# Mircrocontroller-test-moudle.net
KiCad netlist of a schematic drawn in EAGLE
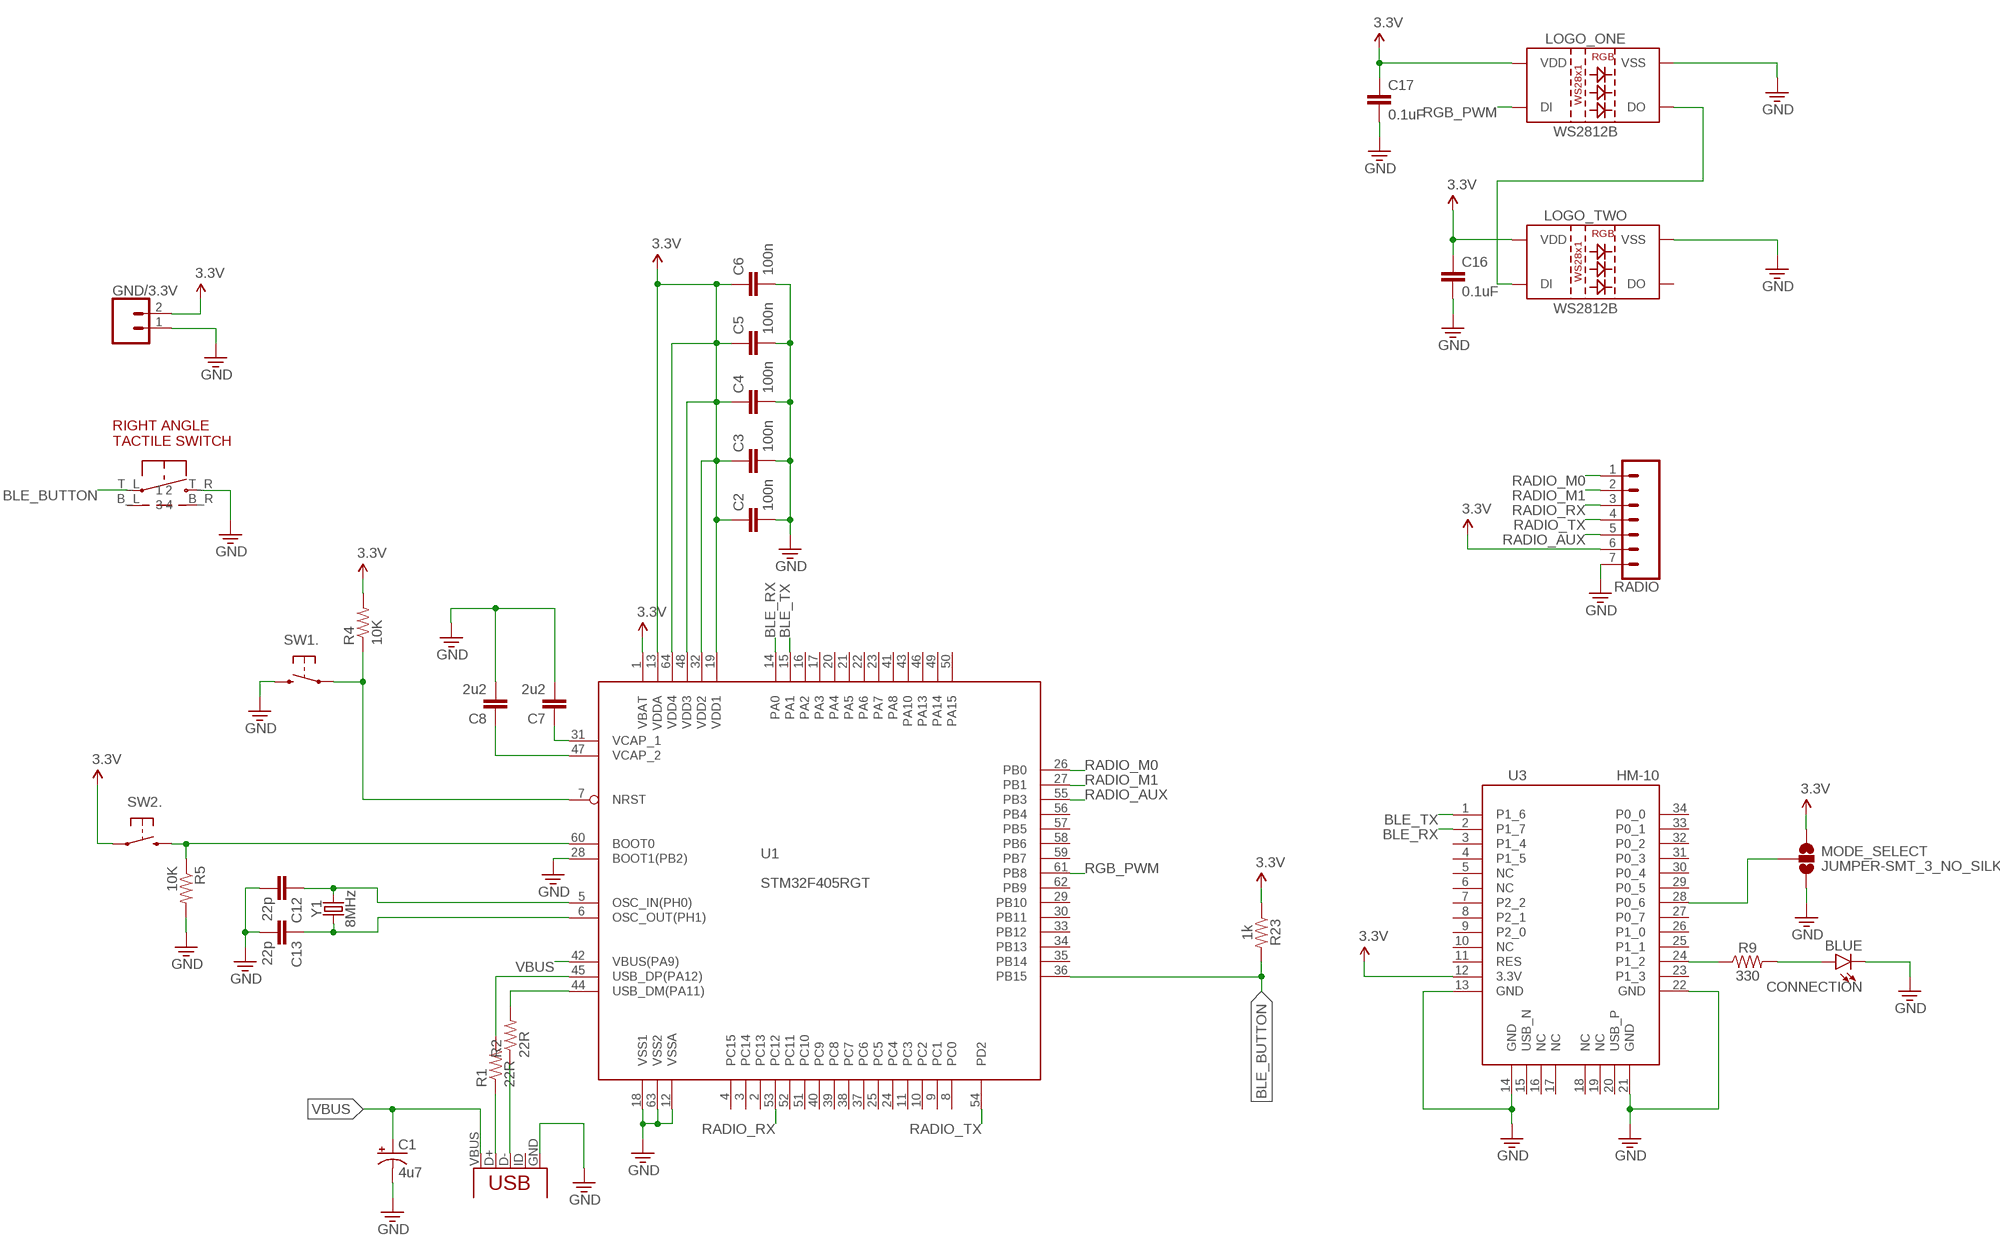
[diagram p0: schematic, sheet 1]

(export (version "E")
  (design (tool "Eeschema 10.0.6"))
  (components
    (comp (ref "C1")
      (value "4u7")
      (footprint "eagle-import:EIA3216-KIT")
      (libsource (lib "eagle-import") (part "CAP_POL1206-KIT"))
    )
    (comp (ref "C2")
      (value "100n")
      (footprint "eagle-import:0603-CAP")
      (libsource (lib "eagle-import") (part "CAP0603-CAP"))
    )
    (comp (ref "C3")
      (value "100n")
      (footprint "eagle-import:0603-CAP")
      (libsource (lib "eagle-import") (part "CAP0603-CAP"))
    )
    (comp (ref "C4")
      (value "100n")
      (footprint "eagle-import:0603-CAP")
      (libsource (lib "eagle-import") (part "CAP0603-CAP"))
    )
    (comp (ref "C5")
      (value "100n")
      (footprint "eagle-import:0603-CAP")
      (libsource (lib "eagle-import") (part "CAP0603-CAP"))
    )
    (comp (ref "C6")
      (value "100n")
      (footprint "eagle-import:0603-CAP")
      (libsource (lib "eagle-import") (part "CAP0603-CAP"))
    )
    (comp (ref "C7")
      (value "2u2")
      (footprint "eagle-import:0603-CAP")
      (libsource (lib "eagle-import") (part "CAP0603-CAP"))
    )
    (comp (ref "C8")
      (value "2u2")
      (footprint "eagle-import:0603-CAP")
      (libsource (lib "eagle-import") (part "CAP0603-CAP"))
    )
    (comp (ref "C12")
      (value "22p")
      (footprint "eagle-import:0603-CAP")
      (libsource (lib "eagle-import") (part "CAP0603-CAP"))
    )
    (comp (ref "C13")
      (value "22p")
      (footprint "eagle-import:0603-CAP")
      (libsource (lib "eagle-import") (part "CAP0603-CAP"))
    )
    (comp (ref "C16")
      (value "0.1uF")
      (footprint "eagle-import:0603")
      (libsource (lib "eagle-import") (part "0.1UF-0603-25V-5%"))
    )
    (comp (ref "C17")
      (value "0.1uF")
      (footprint "eagle-import:0603")
      (libsource (lib "eagle-import") (part "0.1UF-0603-25V-5%"))
    )
    (comp (ref "CONNECTION")
      (value "BLUE")
      (footprint "eagle-import:LED-0603")
      (libsource (lib "eagle-import") (part "LED-BLUE0603"))
    )
    (comp (ref "GND/3.3V")
      (value "CONN_02LOCK")
      (footprint "eagle-import:1X02_LOCK")
      (libsource (lib "eagle-import") (part "CONN_02LOCK"))
    )
    (comp (ref "LOGO_ONE")
      (value "WS2812B")
      (footprint "eagle-import:WS2812B")
      (libsource (lib "eagle-import") (part "WS2812B"))
    )
    (comp (ref "LOGO_TWO")
      (value "WS2812B")
      (footprint "eagle-import:WS2812B")
      (libsource (lib "eagle-import") (part "WS2812B"))
    )
    (comp (ref "MODE_SELECT")
      (value "JUMPER-SMT_3_NO_SILK")
      (footprint "eagle-import:SMT-JUMPER_3_NO_SILK")
      (libsource (lib "eagle-import") (part "JUMPER-SMT_3_NO_SILK"))
    )
    (comp (ref "R1")
      (value "22R")
      (footprint "eagle-import:0603-RES")
      (libsource (lib "eagle-import") (part "RESISTOR0603-RES"))
    )
    (comp (ref "R2")
      (value "22R")
      (footprint "eagle-import:0603-RES")
      (libsource (lib "eagle-import") (part "RESISTOR0603-RES"))
    )
    (comp (ref "R4")
      (value "10K")
      (footprint "eagle-import:0603-RES")
      (libsource (lib "eagle-import") (part "RESISTOR0603-RES"))
    )
    (comp (ref "R5")
      (value "10K")
      (footprint "eagle-import:0603-RES")
      (libsource (lib "eagle-import") (part "RESISTOR0603-RES"))
    )
    (comp (ref "R9")
      (value "330")
      (footprint "eagle-import:0603")
      (libsource (lib "eagle-import") (part "330OHM-0603-1/10W-1%"))
    )
    (comp (ref "R23")
      (value "1k")
      (footprint "eagle-import:0603")
      (libsource (lib "eagle-import") (part "1KOHM-0603-1/10W-1%"))
    )
    (comp (ref "RADIO")
      (value "CONN_07")
      (footprint "eagle-import:1X07")
      (libsource (lib "eagle-import") (part "CONN_07"))
    )
    (comp (ref "SW1")
      (value "!RST")
      (footprint "eagle-import:SWITCH-TACT-B3U-1100P-B")
      (libsource (lib "eagle-import") (part "SWITCH-B3U-1110-BOSS"))
    )
    (comp (ref "SW2")
      (value "BOOT")
      (footprint "eagle-import:SWITCH-TACT-B3U-1100P-B")
      (libsource (lib "eagle-import") (part "SWITCH-B3U-1110-BOSS"))
    )
    (comp (ref "U$1")
      (value "RIGHT_ANGLE_TACTILE_SWITCH")
      (footprint "eagle-import:RIGHT_ANGLE_TACTILE_SWITCH")
      (libsource (lib "eagle-import") (part "RIGHT_ANGLE_TACTILE_SWITCH"))
    )
    (comp (ref "U1")
      (value "STM32F405RGT")
      (footprint "eagle-import:LQFP64")
      (libsource (lib "eagle-import") (part "STM32F405RGT"))
    )
    (comp (ref "U3")
      (value "HM-10")
      (footprint "eagle-import:HM-10")
      (libsource (lib "eagle-import") (part "HM-10"))
    )
    (comp (ref "USB")
      (value "USB-MICROB-SMD")
      (footprint "eagle-import:USB-MICROB-SMD")
      (libsource (lib "eagle-import") (part "USB-MICROB-SMD"))
    )
    (comp (ref "Y1")
      (value "8MHz")
      (footprint "eagle-import:CRYSTAL-SMD-5X3.2-4PAD")
      (libsource (lib "eagle-import") (part "CRYSTAL-8MHZSMD-5X3.2"))
    )
  )
  (nets
    (net (code "1") (name "/BLE_RX") (class "Default")
      (node (ref "U1") (pin "14") (pinfunction "PA0_14") (pintype "bidirectional"))
      (node (ref "U3") (pin "2") (pinfunction "P1_7_2") (pintype "bidirectional"))
    )
    (net (code "2") (name "/BLE_TX") (class "Default")
      (node (ref "U1") (pin "15") (pinfunction "PA1_15") (pintype "bidirectional"))
      (node (ref "U3") (pin "1") (pinfunction "P1_6_1") (pintype "bidirectional"))
    )
    (net (code "3") (name "/RADIO_AUX") (class "Default")
      (node (ref "RADIO") (pin "5") (pinfunction "5_5") (pintype "passive"))
      (node (ref "U1") (pin "55") (pinfunction "PB3_55") (pintype "bidirectional"))
    )
    (net (code "4") (name "/RADIO_M0") (class "Default")
      (node (ref "RADIO") (pin "1") (pinfunction "1_1") (pintype "passive"))
      (node (ref "U1") (pin "26") (pinfunction "PB0_26") (pintype "bidirectional"))
    )
    (net (code "5") (name "/RADIO_M1") (class "Default")
      (node (ref "RADIO") (pin "2") (pinfunction "2_2") (pintype "passive"))
      (node (ref "U1") (pin "27") (pinfunction "PB1_27") (pintype "bidirectional"))
    )
    (net (code "6") (name "/RADIO_RX") (class "Default")
      (node (ref "RADIO") (pin "3") (pinfunction "3_3") (pintype "passive"))
      (node (ref "U1") (pin "53") (pinfunction "PC12_53") (pintype "bidirectional"))
    )
    (net (code "7") (name "/RADIO_TX") (class "Default")
      (node (ref "RADIO") (pin "4") (pinfunction "4_4") (pintype "passive"))
      (node (ref "U1") (pin "54") (pinfunction "PD2_54") (pintype "bidirectional"))
    )
    (net (code "8") (name "/RGB_PWM") (class "Default")
      (node (ref "LOGO_ONE") (pin "4") (pinfunction "DI_4") (pintype "bidirectional"))
      (node (ref "U1") (pin "61") (pinfunction "PB8_61") (pintype "bidirectional"))
    )
    (net (code "9") (name "3.3V") (class "Default")
      (node (ref "C16") (pin "1") (pinfunction "1_1") (pintype "passive"))
      (node (ref "C17") (pin "1") (pinfunction "1_1") (pintype "passive"))
      (node (ref "C2") (pin "1") (pinfunction "1_1") (pintype "passive"))
      (node (ref "C3") (pin "1") (pinfunction "1_1") (pintype "passive"))
      (node (ref "C4") (pin "1") (pinfunction "1_1") (pintype "passive"))
      (node (ref "C5") (pin "1") (pinfunction "1_1") (pintype "passive"))
      (node (ref "C6") (pin "1") (pinfunction "1_1") (pintype "passive"))
      (node (ref "GND/3.3V") (pin "2") (pinfunction "2_2") (pintype "passive"))
      (node (ref "LOGO_ONE") (pin "1") (pinfunction "VDD_1") (pintype "bidirectional"))
      (node (ref "LOGO_TWO") (pin "1") (pinfunction "VDD_1") (pintype "bidirectional"))
      (node (ref "MODE_SELECT") (pin "1") (pinfunction "1_1") (pintype "passive"))
      (node (ref "R23") (pin "1") (pinfunction "1_1") (pintype "passive"))
      (node (ref "R4") (pin "2") (pinfunction "2_2") (pintype "passive"))
      (node (ref "RADIO") (pin "6") (pinfunction "6_6") (pintype "passive"))
      (node (ref "SW2") (pin "1") (pinfunction "1_1") (pintype "passive"))
      (node (ref "U1") (pin "1") (pinfunction "VBAT_1") (pintype "power_in"))
      (node (ref "U1") (pin "13") (pinfunction "VDDA_13") (pintype "power_in"))
      (node (ref "U1") (pin "19") (pinfunction "VDD1_19") (pintype "power_in"))
      (node (ref "U1") (pin "32") (pinfunction "VDD2_32") (pintype "power_in"))
      (node (ref "U1") (pin "48") (pinfunction "VDD3_48") (pintype "power_in"))
      (node (ref "U1") (pin "64") (pinfunction "VDD4_64") (pintype "power_in"))
      (node (ref "U3") (pin "12") (pinfunction "3.3V_12") (pintype "bidirectional"))
    )
    (net (code "10") (name "BLE_BUTTON") (class "Default")
      (node (ref "R23") (pin "2") (pinfunction "2_2") (pintype "passive"))
      (node (ref "U$1") (pin "T_L") (pinfunction "1_T_L") (pintype "bidirectional"))
      (node (ref "U1") (pin "36") (pinfunction "PB15_36") (pintype "bidirectional"))
    )
    (net (code "11") (name "GND") (class "Default")
      (node (ref "C1") (pin "C") (pinfunction "-_C") (pintype "passive"))
      (node (ref "C12") (pin "2") (pinfunction "2_2") (pintype "passive"))
      (node (ref "C13") (pin "2") (pinfunction "2_2") (pintype "passive"))
      (node (ref "C16") (pin "2") (pinfunction "2_2") (pintype "passive"))
      (node (ref "C17") (pin "2") (pinfunction "2_2") (pintype "passive"))
      (node (ref "C2") (pin "2") (pinfunction "2_2") (pintype "passive"))
      (node (ref "C3") (pin "2") (pinfunction "2_2") (pintype "passive"))
      (node (ref "C4") (pin "2") (pinfunction "2_2") (pintype "passive"))
      (node (ref "C5") (pin "2") (pinfunction "2_2") (pintype "passive"))
      (node (ref "C6") (pin "2") (pinfunction "2_2") (pintype "passive"))
      (node (ref "C7") (pin "2") (pinfunction "2_2") (pintype "passive"))
      (node (ref "C8") (pin "2") (pinfunction "2_2") (pintype "passive"))
      (node (ref "CONNECTION") (pin "C") (pinfunction "C_C") (pintype "passive"))
      (node (ref "GND/3.3V") (pin "1") (pinfunction "1_1") (pintype "passive"))
      (node (ref "LOGO_ONE") (pin "3") (pinfunction "VSS_3") (pintype "bidirectional"))
      (node (ref "LOGO_TWO") (pin "3") (pinfunction "VSS_3") (pintype "bidirectional"))
      (node (ref "MODE_SELECT") (pin "3") (pinfunction "3_3") (pintype "passive"))
      (node (ref "R5") (pin "2") (pinfunction "2_2") (pintype "passive"))
      (node (ref "RADIO") (pin "7") (pinfunction "7_7") (pintype "passive"))
      (node (ref "SW1") (pin "2") (pinfunction "2_2") (pintype "passive"))
      (node (ref "U$1") (pin "T_R") (pinfunction "2_T_R") (pintype "bidirectional"))
      (node (ref "U1") (pin "12") (pinfunction "VSSA_12") (pintype "power_in"))
      (node (ref "U1") (pin "18") (pinfunction "VSS1_18") (pintype "power_in"))
      (node (ref "U1") (pin "28") (pinfunction "BOOT1(PB2)_28") (pintype "input"))
      (node (ref "U1") (pin "63") (pinfunction "VSS2_63") (pintype "power_in"))
      (node (ref "U3") (pin "13") (pinfunction "GND_13") (pintype "bidirectional"))
      (node (ref "U3") (pin "14") (pinfunction "GND_14") (pintype "bidirectional"))
      (node (ref "U3") (pin "21") (pinfunction "GND_21") (pintype "bidirectional"))
      (node (ref "U3") (pin "22") (pinfunction "GND_22") (pintype "bidirectional"))
      (node (ref "USB") (pin "GND") (pinfunction "GND_GND") (pintype "bidirectional"))
    )
    (net (code "12") (name "Net-(CONNECTION-PadA)") (class "Default")
      (node (ref "CONNECTION") (pin "A") (pinfunction "A_A") (pintype "passive"))
      (node (ref "R9") (pin "2") (pinfunction "2_2") (pintype "passive"))
    )
    (net (code "13") (name "Net-(LOGO_ONE-DO)") (class "Default")
      (node (ref "LOGO_ONE") (pin "2") (pinfunction "DO_2") (pintype "bidirectional"))
      (node (ref "LOGO_TWO") (pin "4") (pinfunction "DI_4") (pintype "bidirectional"))
    )
    (net (code "14") (name "Net-(R1-Pad1)") (class "Default")
      (node (ref "R1") (pin "1") (pinfunction "1_1") (pintype "passive"))
      (node (ref "USB") (pin "D+") (pinfunction "D+_D+") (pintype "bidirectional"))
    )
    (net (code "15") (name "Net-(R2-Pad1)") (class "Default")
      (node (ref "R2") (pin "1") (pinfunction "1_1") (pintype "passive"))
      (node (ref "USB") (pin "D-") (pinfunction "D-_D-") (pintype "bidirectional"))
    )
    (net (code "16") (name "Net-(U1-BOOT0)") (class "Default")
      (node (ref "R5") (pin "1") (pinfunction "1_1") (pintype "passive"))
      (node (ref "SW2") (pin "2") (pinfunction "2_2") (pintype "passive"))
      (node (ref "U1") (pin "60") (pinfunction "BOOT0_60") (pintype "input"))
    )
    (net (code "17") (name "Net-(U1-NRST)") (class "Default")
      (node (ref "R4") (pin "1") (pinfunction "1_1") (pintype "passive"))
      (node (ref "SW1") (pin "1") (pinfunction "1_1") (pintype "passive"))
      (node (ref "U1") (pin "7") (pinfunction "NRST_7") (pintype "input"))
    )
    (net (code "18") (name "Net-(U1-OSC_IN(PH0))") (class "Default")
      (node (ref "C12") (pin "1") (pinfunction "1_1") (pintype "passive"))
      (node (ref "U1") (pin "5") (pinfunction "OSC_IN(PH0)_5") (pintype "bidirectional"))
      (node (ref "Y1") (pin "3") (pinfunction "2_3") (pintype "passive"))
    )
    (net (code "19") (name "Net-(U1-OSC_OUT(PH1))") (class "Default")
      (node (ref "C13") (pin "1") (pinfunction "1_1") (pintype "passive"))
      (node (ref "U1") (pin "6") (pinfunction "OSC_OUT(PH1)_6") (pintype "bidirectional"))
      (node (ref "Y1") (pin "1") (pinfunction "1_1") (pintype "passive"))
    )
    (net (code "20") (name "Net-(U1-USB_DM(PA11))") (class "Default")
      (node (ref "R2") (pin "2") (pinfunction "2_2") (pintype "passive"))
      (node (ref "U1") (pin "44") (pinfunction "USB_DM(PA11)_44") (pintype "bidirectional"))
    )
    (net (code "21") (name "Net-(U1-USB_DP(PA12))") (class "Default")
      (node (ref "R1") (pin "2") (pinfunction "2_2") (pintype "passive"))
      (node (ref "U1") (pin "45") (pinfunction "USB_DP(PA12)_45") (pintype "bidirectional"))
    )
    (net (code "22") (name "Net-(U1-VCAP_1)") (class "Default")
      (node (ref "C7") (pin "1") (pinfunction "1_1") (pintype "passive"))
      (node (ref "U1") (pin "31") (pinfunction "VCAP_1_31") (pintype "bidirectional"))
    )
    (net (code "23") (name "Net-(U1-VCAP_2)") (class "Default")
      (node (ref "C8") (pin "1") (pinfunction "1_1") (pintype "passive"))
      (node (ref "U1") (pin "47") (pinfunction "VCAP_2_47") (pintype "bidirectional"))
    )
    (net (code "24") (name "Net-(U3-P0_6)") (class "Default")
      (node (ref "MODE_SELECT") (pin "2") (pinfunction "2_2") (pintype "passive"))
      (node (ref "U3") (pin "28") (pinfunction "P0_6_28") (pintype "bidirectional"))
    )
    (net (code "25") (name "Net-(U3-P1_2)") (class "Default")
      (node (ref "R9") (pin "1") (pinfunction "1_1") (pintype "passive"))
      (node (ref "U3") (pin "24") (pinfunction "P1_2_24") (pintype "bidirectional"))
    )
    (net (code "26") (name "VBUS") (class "Default")
      (node (ref "C1") (pin "A") (pinfunction "+_A") (pintype "passive"))
      (node (ref "U1") (pin "42") (pinfunction "VBUS(PA9)_42") (pintype "bidirectional"))
      (node (ref "USB") (pin "VBUS") (pinfunction "VBUS_VBUS") (pintype "bidirectional"))
    )
    (net (code "27") (name "unconnected-(LOGO_TWO-DO-Pad2)") (class "Default")
      (node (ref "LOGO_TWO") (pin "2") (pinfunction "DO_2") (pintype "bidirectional"))
    )
    (net (code "28") (name "unconnected-(U$1-3-PadB_L)") (class "Default")
      (node (ref "U$1") (pin "B_L") (pinfunction "3_B_L") (pintype "bidirectional"))
    )
    (net (code "29") (name "unconnected-(U$1-4-PadB_R)") (class "Default")
      (node (ref "U$1") (pin "B_R") (pinfunction "4_B_R") (pintype "bidirectional"))
    )
    (net (code "30") (name "unconnected-(U1-PA2-Pad16)") (class "Default")
      (node (ref "U1") (pin "16") (pinfunction "PA2_16") (pintype "bidirectional"))
    )
    (net (code "31") (name "unconnected-(U1-PA3-Pad17)") (class "Default")
      (node (ref "U1") (pin "17") (pinfunction "PA3_17") (pintype "bidirectional"))
    )
    (net (code "32") (name "unconnected-(U1-PA4-Pad20)") (class "Default")
      (node (ref "U1") (pin "20") (pinfunction "PA4_20") (pintype "bidirectional"))
    )
    (net (code "33") (name "unconnected-(U1-PA5-Pad21)") (class "Default")
      (node (ref "U1") (pin "21") (pinfunction "PA5_21") (pintype "bidirectional"))
    )
    (net (code "34") (name "unconnected-(U1-PA6-Pad22)") (class "Default")
      (node (ref "U1") (pin "22") (pinfunction "PA6_22") (pintype "bidirectional"))
    )
    (net (code "35") (name "unconnected-(U1-PA7-Pad23)") (class "Default")
      (node (ref "U1") (pin "23") (pinfunction "PA7_23") (pintype "bidirectional"))
    )
    (net (code "36") (name "unconnected-(U1-PA8-Pad41)") (class "Default")
      (node (ref "U1") (pin "41") (pinfunction "PA8_41") (pintype "bidirectional"))
    )
    (net (code "37") (name "unconnected-(U1-PA10-Pad43)") (class "Default")
      (node (ref "U1") (pin "43") (pinfunction "PA10_43") (pintype "bidirectional"))
    )
    (net (code "38") (name "unconnected-(U1-PA13-Pad46)") (class "Default")
      (node (ref "U1") (pin "46") (pinfunction "PA13_46") (pintype "bidirectional"))
    )
    (net (code "39") (name "unconnected-(U1-PA14-Pad49)") (class "Default")
      (node (ref "U1") (pin "49") (pinfunction "PA14_49") (pintype "bidirectional"))
    )
    (net (code "40") (name "unconnected-(U1-PA15-Pad50)") (class "Default")
      (node (ref "U1") (pin "50") (pinfunction "PA15_50") (pintype "bidirectional"))
    )
    (net (code "41") (name "unconnected-(U1-PB4-Pad56)") (class "Default")
      (node (ref "U1") (pin "56") (pinfunction "PB4_56") (pintype "bidirectional"))
    )
    (net (code "42") (name "unconnected-(U1-PB5-Pad57)") (class "Default")
      (node (ref "U1") (pin "57") (pinfunction "PB5_57") (pintype "bidirectional"))
    )
    (net (code "43") (name "unconnected-(U1-PB6-Pad58)") (class "Default")
      (node (ref "U1") (pin "58") (pinfunction "PB6_58") (pintype "bidirectional"))
    )
    (net (code "44") (name "unconnected-(U1-PB7-Pad59)") (class "Default")
      (node (ref "U1") (pin "59") (pinfunction "PB7_59") (pintype "bidirectional"))
    )
    (net (code "45") (name "unconnected-(U1-PB9-Pad62)") (class "Default")
      (node (ref "U1") (pin "62") (pinfunction "PB9_62") (pintype "bidirectional"))
    )
    (net (code "46") (name "unconnected-(U1-PB10-Pad29)") (class "Default")
      (node (ref "U1") (pin "29") (pinfunction "PB10_29") (pintype "bidirectional"))
    )
    (net (code "47") (name "unconnected-(U1-PB11-Pad30)") (class "Default")
      (node (ref "U1") (pin "30") (pinfunction "PB11_30") (pintype "bidirectional"))
    )
    (net (code "48") (name "unconnected-(U1-PB12-Pad33)") (class "Default")
      (node (ref "U1") (pin "33") (pinfunction "PB12_33") (pintype "bidirectional"))
    )
    (net (code "49") (name "unconnected-(U1-PB13-Pad34)") (class "Default")
      (node (ref "U1") (pin "34") (pinfunction "PB13_34") (pintype "bidirectional"))
    )
    (net (code "50") (name "unconnected-(U1-PB14-Pad35)") (class "Default")
      (node (ref "U1") (pin "35") (pinfunction "PB14_35") (pintype "bidirectional"))
    )
    (net (code "51") (name "unconnected-(U1-PC0-Pad8)") (class "Default")
      (node (ref "U1") (pin "8") (pinfunction "PC0_8") (pintype "bidirectional"))
    )
    (net (code "52") (name "unconnected-(U1-PC1-Pad9)") (class "Default")
      (node (ref "U1") (pin "9") (pinfunction "PC1_9") (pintype "bidirectional"))
    )
    (net (code "53") (name "unconnected-(U1-PC2-Pad10)") (class "Default")
      (node (ref "U1") (pin "10") (pinfunction "PC2_10") (pintype "bidirectional"))
    )
    (net (code "54") (name "unconnected-(U1-PC3-Pad11)") (class "Default")
      (node (ref "U1") (pin "11") (pinfunction "PC3_11") (pintype "bidirectional"))
    )
    (net (code "55") (name "unconnected-(U1-PC4-Pad24)") (class "Default")
      (node (ref "U1") (pin "24") (pinfunction "PC4_24") (pintype "bidirectional"))
    )
    (net (code "56") (name "unconnected-(U1-PC5-Pad25)") (class "Default")
      (node (ref "U1") (pin "25") (pinfunction "PC5_25") (pintype "bidirectional"))
    )
    (net (code "57") (name "unconnected-(U1-PC6-Pad37)") (class "Default")
      (node (ref "U1") (pin "37") (pinfunction "PC6_37") (pintype "bidirectional"))
    )
    (net (code "58") (name "unconnected-(U1-PC7-Pad38)") (class "Default")
      (node (ref "U1") (pin "38") (pinfunction "PC7_38") (pintype "bidirectional"))
    )
    (net (code "59") (name "unconnected-(U1-PC8-Pad39)") (class "Default")
      (node (ref "U1") (pin "39") (pinfunction "PC8_39") (pintype "bidirectional"))
    )
    (net (code "60") (name "unconnected-(U1-PC9-Pad40)") (class "Default")
      (node (ref "U1") (pin "40") (pinfunction "PC9_40") (pintype "bidirectional"))
    )
    (net (code "61") (name "unconnected-(U1-PC10-Pad51)") (class "Default")
      (node (ref "U1") (pin "51") (pinfunction "PC10_51") (pintype "bidirectional"))
    )
    (net (code "62") (name "unconnected-(U1-PC11-Pad52)") (class "Default")
      (node (ref "U1") (pin "52") (pinfunction "PC11_52") (pintype "bidirectional"))
    )
    (net (code "63") (name "unconnected-(U1-PC13-Pad2)") (class "Default")
      (node (ref "U1") (pin "2") (pinfunction "PC13_2") (pintype "bidirectional"))
    )
    (net (code "64") (name "unconnected-(U1-PC14-Pad3)") (class "Default")
      (node (ref "U1") (pin "3") (pinfunction "PC14_3") (pintype "bidirectional"))
    )
    (net (code "65") (name "unconnected-(U1-PC15-Pad4)") (class "Default")
      (node (ref "U1") (pin "4") (pinfunction "PC15_4") (pintype "bidirectional"))
    )
    (net (code "66") (name "unconnected-(U3-NC-Pad5)") (class "Default")
      (node (ref "U3") (pin "5") (pinfunction "NC_5") (pintype "bidirectional"))
    )
    (net (code "67") (name "unconnected-(U3-NC-Pad6)") (class "Default")
      (node (ref "U3") (pin "6") (pinfunction "NC_6") (pintype "bidirectional"))
    )
    (net (code "68") (name "unconnected-(U3-NC-Pad10)") (class "Default")
      (node (ref "U3") (pin "10") (pinfunction "NC_10") (pintype "bidirectional"))
    )
    (net (code "69") (name "unconnected-(U3-NC-Pad16)") (class "Default")
      (node (ref "U3") (pin "16") (pinfunction "NC_16") (pintype "bidirectional"))
    )
    (net (code "70") (name "unconnected-(U3-NC-Pad17)") (class "Default")
      (node (ref "U3") (pin "17") (pinfunction "NC_17") (pintype "bidirectional"))
    )
    (net (code "71") (name "unconnected-(U3-NC-Pad18)") (class "Default")
      (node (ref "U3") (pin "18") (pinfunction "NC_18") (pintype "bidirectional"))
    )
    (net (code "72") (name "unconnected-(U3-NC-Pad19)") (class "Default")
      (node (ref "U3") (pin "19") (pinfunction "NC_19") (pintype "bidirectional"))
    )
    (net (code "73") (name "unconnected-(U3-P0_0-Pad34)") (class "Default")
      (node (ref "U3") (pin "34") (pinfunction "P0_0_34") (pintype "bidirectional"))
    )
    (net (code "74") (name "unconnected-(U3-P0_1-Pad33)") (class "Default")
      (node (ref "U3") (pin "33") (pinfunction "P0_1_33") (pintype "bidirectional"))
    )
    (net (code "75") (name "unconnected-(U3-P0_2-Pad32)") (class "Default")
      (node (ref "U3") (pin "32") (pinfunction "P0_2_32") (pintype "bidirectional"))
    )
    (net (code "76") (name "unconnected-(U3-P0_3-Pad31)") (class "Default")
      (node (ref "U3") (pin "31") (pinfunction "P0_3_31") (pintype "bidirectional"))
    )
    (net (code "77") (name "unconnected-(U3-P0_4-Pad30)") (class "Default")
      (node (ref "U3") (pin "30") (pinfunction "P0_4_30") (pintype "bidirectional"))
    )
    (net (code "78") (name "unconnected-(U3-P0_5-Pad29)") (class "Default")
      (node (ref "U3") (pin "29") (pinfunction "P0_5_29") (pintype "bidirectional"))
    )
    (net (code "79") (name "unconnected-(U3-P0_7-Pad27)") (class "Default")
      (node (ref "U3") (pin "27") (pinfunction "P0_7_27") (pintype "bidirectional"))
    )
    (net (code "80") (name "unconnected-(U3-P1_0-Pad26)") (class "Default")
      (node (ref "U3") (pin "26") (pinfunction "P1_0_26") (pintype "bidirectional"))
    )
    (net (code "81") (name "unconnected-(U3-P1_1-Pad25)") (class "Default")
      (node (ref "U3") (pin "25") (pinfunction "P1_1_25") (pintype "bidirectional"))
    )
    (net (code "82") (name "unconnected-(U3-P1_3-Pad23)") (class "Default")
      (node (ref "U3") (pin "23") (pinfunction "P1_3_23") (pintype "bidirectional"))
    )
    (net (code "83") (name "unconnected-(U3-P1_4-Pad3)") (class "Default")
      (node (ref "U3") (pin "3") (pinfunction "P1_4_3") (pintype "bidirectional"))
    )
    (net (code "84") (name "unconnected-(U3-P1_5-Pad4)") (class "Default")
      (node (ref "U3") (pin "4") (pinfunction "P1_5_4") (pintype "bidirectional"))
    )
    (net (code "85") (name "unconnected-(U3-P2_0-Pad9)") (class "Default")
      (node (ref "U3") (pin "9") (pinfunction "P2_0_9") (pintype "bidirectional"))
    )
    (net (code "86") (name "unconnected-(U3-P2_1-Pad8)") (class "Default")
      (node (ref "U3") (pin "8") (pinfunction "P2_1_8") (pintype "bidirectional"))
    )
    (net (code "87") (name "unconnected-(U3-P2_2-Pad7)") (class "Default")
      (node (ref "U3") (pin "7") (pinfunction "P2_2_7") (pintype "bidirectional"))
    )
    (net (code "88") (name "unconnected-(U3-RES-Pad11)") (class "Default")
      (node (ref "U3") (pin "11") (pinfunction "RES_11") (pintype "bidirectional"))
    )
    (net (code "89") (name "unconnected-(U3-USB_N-Pad15)") (class "Default")
      (node (ref "U3") (pin "15") (pinfunction "USB_N_15") (pintype "bidirectional"))
    )
    (net (code "90") (name "unconnected-(U3-USB_P-Pad20)") (class "Default")
      (node (ref "U3") (pin "20") (pinfunction "USB_P_20") (pintype "bidirectional"))
    )
    (net (code "91") (name "unconnected-(USB-PadID)") (class "Default")
      (node (ref "USB") (pin "ID") (pinfunction "ID_ID") (pintype "bidirectional"))
    )
  )
)
